# wifi-bt.net
KiCad netlist of a schematic drawn in Altium Designer
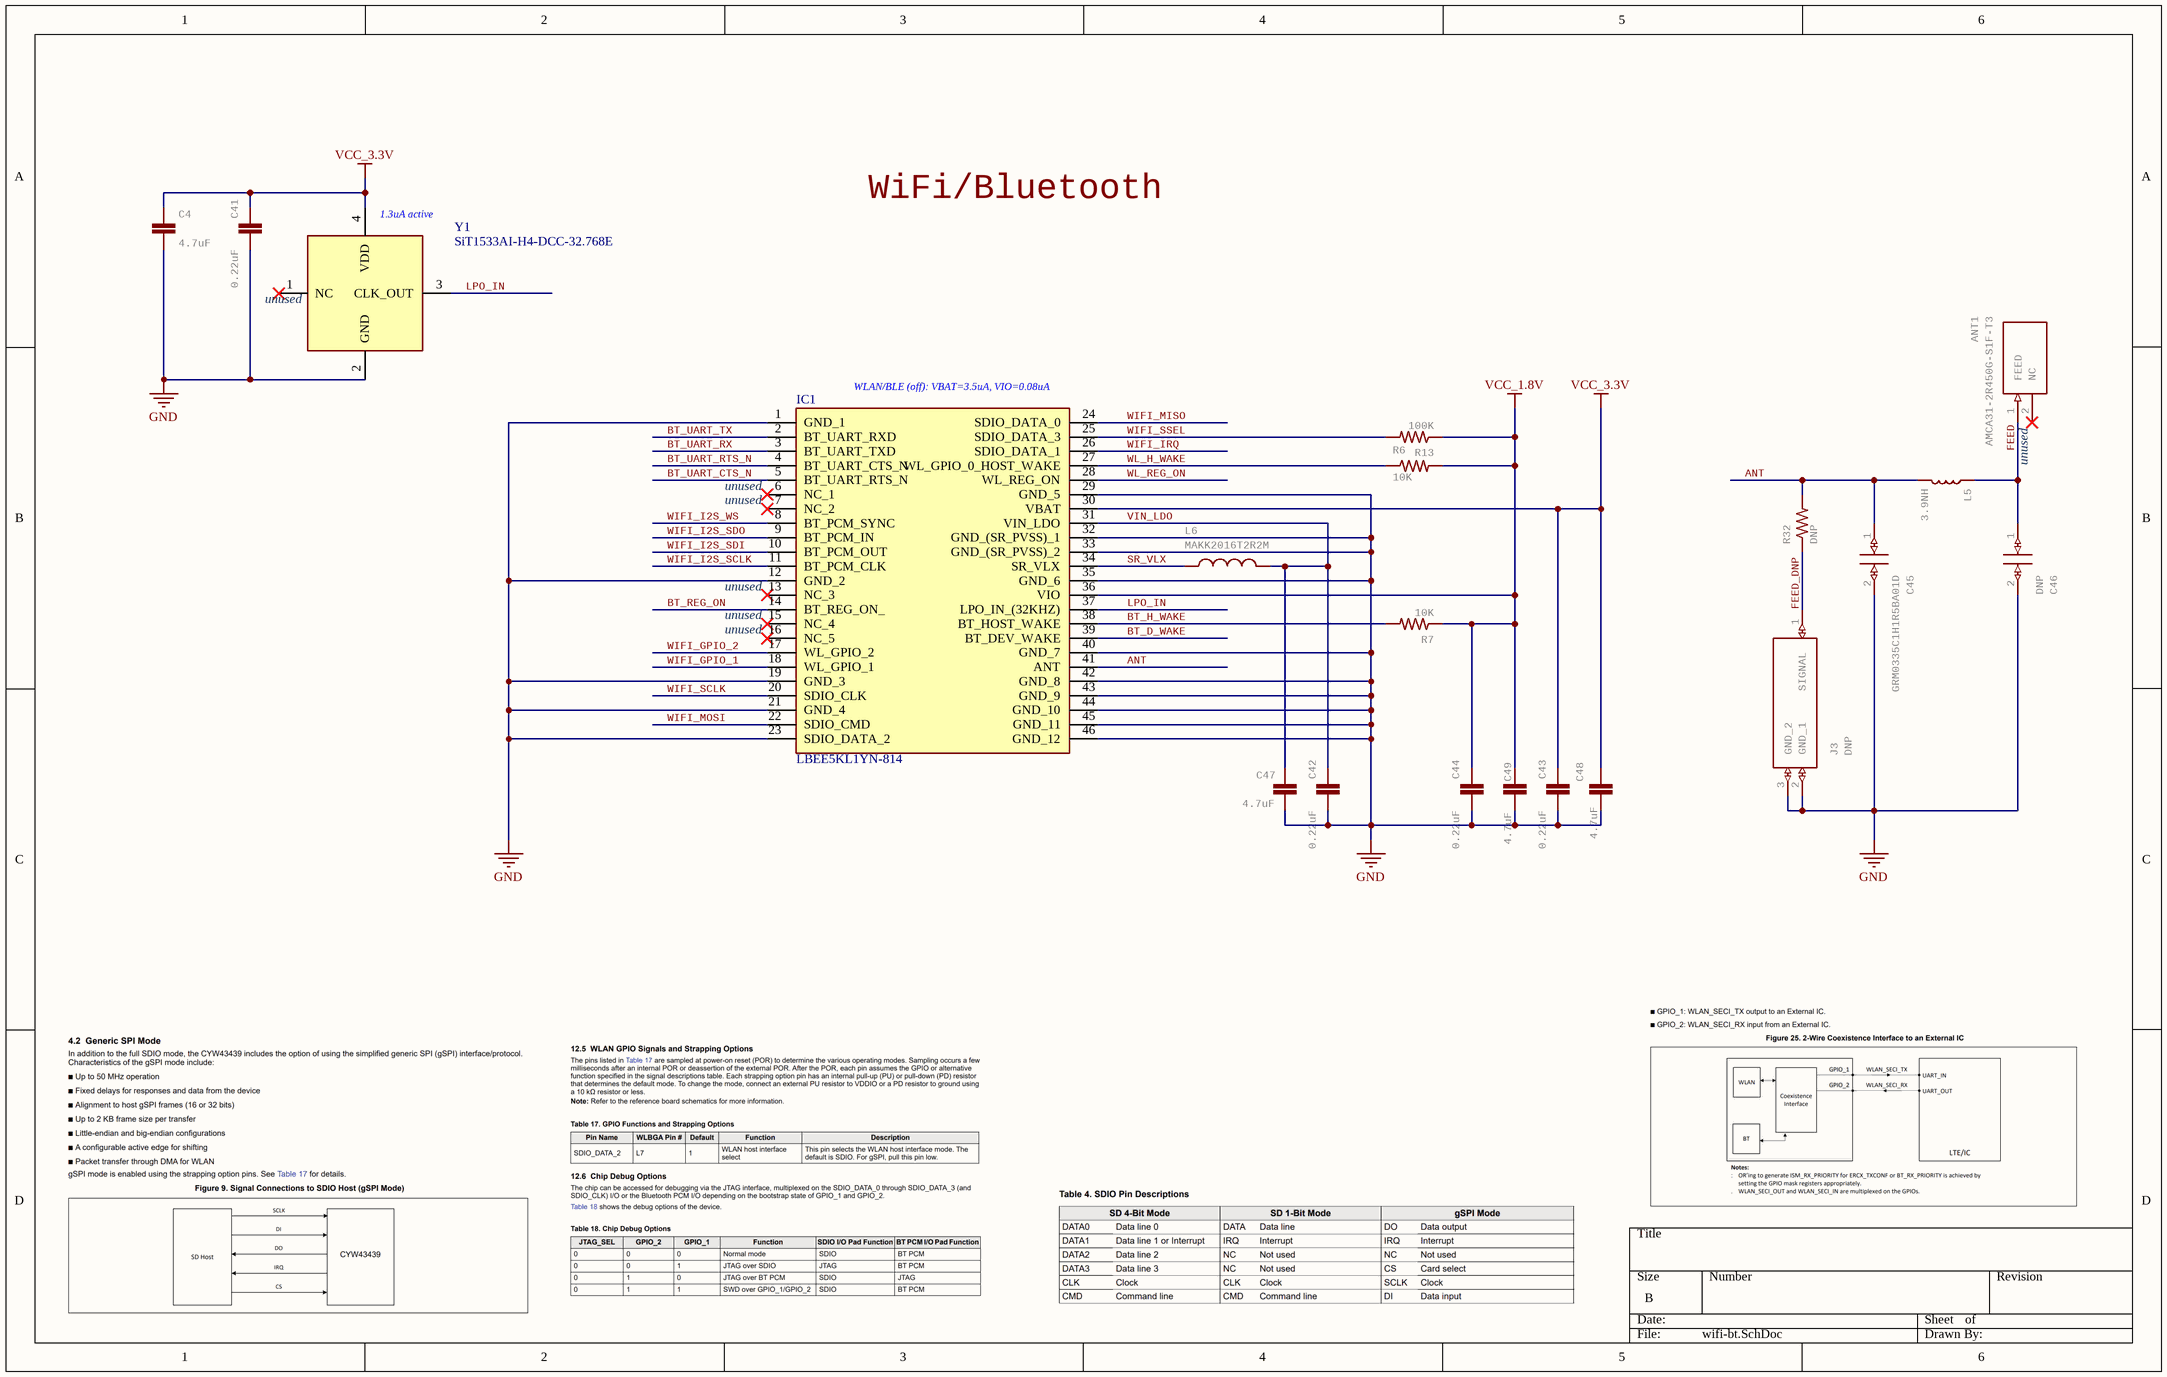
[diagram p0: wifi-bt.SchDoc]

(export (version "E")
  (design (tool "Eeschema 10.0.6"))
  (components
    (comp (ref "ANT1")
      (value "AMCA31-2R450G-S1F-T3")
      (footprint "ANTC3216X140N")
      (description "ABRACON - AMCA31-2R450G-S1F-T3 - ANTENNA, CHIP, 2.45GHZ, 50 OHM, 1206   Source:  Datasheet")
      (fields (field (name "MOUSER_PART_NUMBER") "815-CA312R450GS1FT3"))
      (libsource (lib "openmv-ae3") (part "AMCA31-2R450G-S1F-T3"))
    )
    (comp (ref "C4")
      (value "4.7uF")
      (footprint "0402-CAP")
      (description "CapacitorStandard 0603 ceramic capacitor, and 0.1\" leaded capacitor.")
      (fields (field (name "MPN") "JMK105BBJ475MV-F") (field (name "LIBRARYNAME") "sfe"))
      (libsource (lib "openmv-ae3") (part "CAP0402-CAP"))
    )
    (comp (ref "C41")
      (value "0.22uF")
      (footprint "C0201")
      (description "CAPACITOR, European symbol")
      (fields (field (name "MPN") "GRM033R60J224ME15D"))
      (libsource (lib "openmv-ae3") (part "C-EUC0201"))
    )
    (comp (ref "C42")
      (value "0.22uF")
      (footprint "C0201")
      (description "CAPACITOR, European symbol")
      (fields (field (name "MPN") "GRM033R60J224ME15D"))
      (libsource (lib "openmv-ae3") (part "C-EUC0201"))
    )
    (comp (ref "C43")
      (value "0.22uF")
      (footprint "C0201")
      (description "CAPACITOR, European symbol")
      (fields (field (name "MPN") "GRM033R60J224ME15D"))
      (libsource (lib "openmv-ae3") (part "C-EUC0201"))
    )
    (comp (ref "C44")
      (value "0.22uF")
      (footprint "C0201")
      (description "CAPACITOR, European symbol")
      (fields (field (name "MPN") "GRM033R60J224ME15D"))
      (libsource (lib "openmv-ae3") (part "C-EUC0201"))
    )
    (comp (ref "C45")
      (value "GRM0335C1H1R5BA01D")
      (footprint "CAPC0603X33N")
      (description "Chip Capacitor value 1R5   Source:  Datasheet")
      (fields (field (name "MOUSER_PART_NUMBER") "81-GRM0335C1H1R5BA1D"))
      (libsource (lib "openmv-ae3") (part "GRM0335C1H1R5BA01D"))
    )
    (comp (ref "C46")
      (value "DNP")
      (footprint "C0201-NO-3D")
      (description "Chip Capacitor value 1R5   Source:  Datasheet")
      (fields
        (field (name "MANUFACTURER_PART_NUMBER") "GRM0335C1H1R5BA01D")
        (field (name "MOUSER_PART_NUMBER") "81-GRM0335C1H1R5BA1D")
      )
      (libsource (lib "openmv-ae3") (part "GRM0335C1H1R5BA01D"))
    )
    (comp (ref "C47")
      (value "4.7uF")
      (footprint "0402-CAP")
      (description "CapacitorStandard 0603 ceramic capacitor, and 0.1\" leaded capacitor.")
      (fields (field (name "MPN") "JMK105BBJ475MV-F") (field (name "LIBRARYNAME") "sfe"))
      (libsource (lib "openmv-ae3") (part "CAP0402-CAP"))
    )
    (comp (ref "C48")
      (value "4.7uF")
      (footprint "0402-CAP")
      (description "CapacitorStandard 0603 ceramic capacitor, and 0.1\" leaded capacitor.")
      (fields (field (name "MPN") "JMK105BBJ475MV-F") (field (name "LIBRARYNAME") "sfe"))
      (libsource (lib "openmv-ae3") (part "CAP0402-CAP"))
    )
    (comp (ref "C49")
      (value "4.7uF")
      (footprint "0402-CAP")
      (description "CapacitorStandard 0603 ceramic capacitor, and 0.1\" leaded capacitor.")
      (fields (field (name "MPN") "JMK105BBJ475MV-F") (field (name "LIBRARYNAME") "sfe"))
      (libsource (lib "openmv-ae3") (part "CAP0402-CAP"))
    )
    (comp (ref "IC1")
      (value "LBEE5KL1YN-814")
      (footprint "SamacSys:LBEE5KL1YN814")
      (description "Integrated Circuit")
      (fields (field (name "MOUSER PART NUMBER") "81-LBEE5KL1YN-814"))
      (libsource (lib "openmv-ae3") (part "LBEE5KL1YN-814"))
    )
    (comp (ref "J3")
      (value "DNP")
      (footprint "23370191-NO-3D")
      (description "RF Connectors / Coaxial Connectors MicroCoax receptacle UMCC Gen 1   Source:  Datasheet")
      (fields
        (field (name "MANUFACTURER_PART_NUMBER") "2337019-1")
        (field (name "MOUSER_PART_NUMBER") "571-2337019-1")
      )
      (libsource (lib "openmv-ae3") (part "2337019-1"))
    )
    (comp (ref "L5")
      (value "3.9NH")
      (footprint "0402")
      (fields (field (name "MPN") "L-07C3N9SV6T") (field (name "LIBRARYNAME") "SparkFun-Coils"))
      (libsource (lib "openmv-ae3") (part "INDUCTOR-0402-3.9NH"))
    )
    (comp (ref "L6")
      (value "MAKK2016T2R2M")
      (footprint "INDC2016X100N")
      (description "INDUCTOR, METAL CORE Check availability")
      (fields (field (name "MF") "Taiyo Yuden"))
      (libsource (lib "openmv-ae3") (part "MAKK2016T2R2M"))
    )
    (comp (ref "R6")
      (value "10K")
      (footprint "R0201")
      (fields (field (name "MPN") "RMCF0201FT10K0") (field (name "LIBRARYNAME") "sfe"))
      (libsource (lib "openmv-ae3") (part "RESISTOR0402-RES"))
    )
    (comp (ref "R7")
      (value "10K")
      (footprint "R0201")
      (fields (field (name "MPN") "RMCF0201FT10K0") (field (name "LIBRARYNAME") "sfe"))
      (libsource (lib "openmv-ae3") (part "RESISTOR0402-RES"))
    )
    (comp (ref "R13")
      (value "100K")
      (footprint "R0201")
      (fields (field (name "MPN") "RMCF0201FT100K") (field (name "LIBRARYNAME") "sfe"))
      (libsource (lib "openmv-ae3") (part "RESISTOR0402-RES"))
    )
    (comp (ref "R32")
      (value "DNP")
      (footprint "R0201")
      (fields (field (name "LIBRARYNAME") "sfe"))
      (libsource (lib "openmv-ae3") (part "RESISTOR0402-RES"))
    )
    (comp (ref "Y1")
      (value "SiT1533AI-H4-DCC-32.768E")
      (footprint "SamacSys:SIT1533AIH4AA332768E")
      (description "Crystal or Oscillator")
      (fields (field (name "MOUSER PART NUMBER") "788-1533AIH4DCC32.76"))
      (libsource (lib "openmv-ae3") (part "SIT1533AI-H4-AA3-32.768E"))
    )
  )
  (nets
    (net (code "1") (name "/ANT") (class "Default")
      (node (ref "C45") (pin "1") (pinfunction "1_1") (pintype "bidirectional"))
      (node (ref "IC1") (pin "41") (pinfunction "ANT_41") (pintype "passive"))
      (node (ref "L5") (pin "2") (pinfunction "2_2") (pintype "passive"))
      (node (ref "R32") (pin "2") (pinfunction "2_2") (pintype "passive"))
    )
    (net (code "2") (name "/BT_D_WAKE") (class "Default")
      (node (ref "IC1") (pin "39") (pinfunction "BT_DEV_WAKE_39") (pintype "passive"))
    )
    (net (code "3") (name "/BT_H_WAKE") (class "Default")
      (node (ref "IC1") (pin "38") (pinfunction "BT_HOST_WAKE_38") (pintype "passive"))
      (node (ref "R7") (pin "2") (pinfunction "2_2") (pintype "passive"))
    )
    (net (code "4") (name "/BT_REG_ON") (class "Default")
      (node (ref "IC1") (pin "14") (pinfunction "BT_REG_ON__14") (pintype "passive"))
    )
    (net (code "5") (name "/BT_UART_CTS_N") (class "Default")
      (node (ref "IC1") (pin "5") (pinfunction "BT_UART_RTS_N_5") (pintype "passive"))
    )
    (net (code "6") (name "/BT_UART_RTS_N") (class "Default")
      (node (ref "IC1") (pin "4") (pinfunction "BT_UART_CTS_N_4") (pintype "passive"))
    )
    (net (code "7") (name "/BT_UART_RX") (class "Default")
      (node (ref "IC1") (pin "3") (pinfunction "BT_UART_TXD_3") (pintype "passive"))
    )
    (net (code "8") (name "/BT_UART_TX") (class "Default")
      (node (ref "IC1") (pin "2") (pinfunction "BT_UART_RXD_2") (pintype "passive"))
    )
    (net (code "9") (name "/FEED") (class "Default")
      (node (ref "ANT1") (pin "1") (pinfunction "FEED_1") (pintype "input"))
      (node (ref "C46") (pin "1") (pinfunction "1_1") (pintype "bidirectional"))
      (node (ref "L5") (pin "1") (pinfunction "1_1") (pintype "passive"))
    )
    (net (code "10") (name "/FEED_DNP") (class "Default")
      (node (ref "J3") (pin "1") (pinfunction "SIGNAL_1") (pintype "bidirectional"))
      (node (ref "R32") (pin "1") (pinfunction "1_1") (pintype "passive"))
    )
    (net (code "11") (name "/LPO_IN") (class "Default")
      (node (ref "IC1") (pin "37") (pinfunction "LPO_IN_(32KHZ)_37") (pintype "passive"))
      (node (ref "Y1") (pin "3") (pinfunction "CLK_OUT_3") (pintype "passive"))
    )
    (net (code "12") (name "/SR_VLX") (class "Default")
      (node (ref "IC1") (pin "34") (pinfunction "SR_VLX_34") (pintype "passive"))
      (node (ref "L6") (pin "1") (pinfunction "1_1") (pintype "passive"))
    )
    (net (code "13") (name "/VIN_LDO") (class "Default")
      (node (ref "C42") (pin "1") (pinfunction "1_1") (pintype "passive"))
      (node (ref "C47") (pin "2") (pinfunction "2_2") (pintype "passive"))
      (node (ref "IC1") (pin "31") (pinfunction "VIN_LDO_31") (pintype "passive"))
      (node (ref "L6") (pin "2") (pinfunction "2_2") (pintype "passive"))
    )
    (net (code "14") (name "/WIFI_GPIO_1") (class "Default")
      (node (ref "IC1") (pin "18") (pinfunction "WL_GPIO_1_18") (pintype "passive"))
    )
    (net (code "15") (name "/WIFI_GPIO_2") (class "Default")
      (node (ref "IC1") (pin "17") (pinfunction "WL_GPIO_2_17") (pintype "passive"))
    )
    (net (code "16") (name "/WIFI_I2S_SCLK") (class "Default")
      (node (ref "IC1") (pin "11") (pinfunction "BT_PCM_CLK_11") (pintype "passive"))
    )
    (net (code "17") (name "/WIFI_I2S_SDI") (class "Default")
      (node (ref "IC1") (pin "10") (pinfunction "BT_PCM_OUT_10") (pintype "passive"))
    )
    (net (code "18") (name "/WIFI_I2S_SDO") (class "Default")
      (node (ref "IC1") (pin "9") (pinfunction "BT_PCM_IN_9") (pintype "passive"))
    )
    (net (code "19") (name "/WIFI_I2S_WS") (class "Default")
      (node (ref "IC1") (pin "8") (pinfunction "BT_PCM_SYNC_8") (pintype "passive"))
    )
    (net (code "20") (name "/WIFI_IRQ") (class "Default")
      (node (ref "IC1") (pin "26") (pinfunction "SDIO_DATA_1_26") (pintype "passive"))
    )
    (net (code "21") (name "/WIFI_MISO") (class "Default")
      (node (ref "IC1") (pin "24") (pinfunction "SDIO_DATA_0_24") (pintype "passive"))
    )
    (net (code "22") (name "/WIFI_MOSI") (class "Default")
      (node (ref "IC1") (pin "22") (pinfunction "SDIO_CMD_22") (pintype "passive"))
    )
    (net (code "23") (name "/WIFI_SCLK") (class "Default")
      (node (ref "IC1") (pin "20") (pinfunction "SDIO_CLK_20") (pintype "passive"))
    )
    (net (code "24") (name "/WIFI_SSEL") (class "Default")
      (node (ref "IC1") (pin "25") (pinfunction "SDIO_DATA_3_25") (pintype "passive"))
      (node (ref "R13") (pin "2") (pinfunction "2_2") (pintype "passive"))
    )
    (net (code "25") (name "/WL_H_WAKE") (class "Default")
      (node (ref "IC1") (pin "27") (pinfunction "WL_GPIO_0_HOST_WAKE_27") (pintype "passive"))
      (node (ref "R6") (pin "1") (pinfunction "1_1") (pintype "passive"))
    )
    (net (code "26") (name "/WL_REG_ON") (class "Default")
      (node (ref "IC1") (pin "28") (pinfunction "WL_REG_ON_28") (pintype "passive"))
    )
    (net (code "27") (name "GND") (class "Default")
      (node (ref "C4") (pin "1") (pinfunction "1_1") (pintype "passive"))
      (node (ref "C41") (pin "2") (pinfunction "2_2") (pintype "passive"))
      (node (ref "C42") (pin "2") (pinfunction "2_2") (pintype "passive"))
      (node (ref "C43") (pin "2") (pinfunction "2_2") (pintype "passive"))
      (node (ref "C44") (pin "2") (pinfunction "2_2") (pintype "passive"))
      (node (ref "C45") (pin "2") (pinfunction "2_2") (pintype "bidirectional"))
      (node (ref "C46") (pin "2") (pinfunction "2_2") (pintype "bidirectional"))
      (node (ref "C47") (pin "1") (pinfunction "1_1") (pintype "passive"))
      (node (ref "C48") (pin "1") (pinfunction "1_1") (pintype "passive"))
      (node (ref "C49") (pin "1") (pinfunction "1_1") (pintype "passive"))
      (node (ref "IC1") (pin "1") (pinfunction "GND_1_1") (pintype "passive"))
      (node (ref "IC1") (pin "12") (pinfunction "GND_2_12") (pintype "passive"))
      (node (ref "IC1") (pin "19") (pinfunction "GND_3_19") (pintype "passive"))
      (node (ref "IC1") (pin "21") (pinfunction "GND_4_21") (pintype "passive"))
      (node (ref "IC1") (pin "23") (pinfunction "SDIO_DATA_2_23") (pintype "passive"))
      (node (ref "IC1") (pin "29") (pinfunction "GND_5_29") (pintype "passive"))
      (node (ref "IC1") (pin "32") (pinfunction "GND_(SR_PVSS)_1_32") (pintype "passive"))
      (node (ref "IC1") (pin "33") (pinfunction "GND_(SR_PVSS)_2_33") (pintype "passive"))
      (node (ref "IC1") (pin "35") (pinfunction "GND_6_35") (pintype "passive"))
      (node (ref "IC1") (pin "40") (pinfunction "GND_7_40") (pintype "passive"))
      (node (ref "IC1") (pin "42") (pinfunction "GND_8_42") (pintype "passive"))
      (node (ref "IC1") (pin "43") (pinfunction "GND_9_43") (pintype "passive"))
      (node (ref "IC1") (pin "44") (pinfunction "GND_10_44") (pintype "passive"))
      (node (ref "IC1") (pin "45") (pinfunction "GND_11_45") (pintype "passive"))
      (node (ref "IC1") (pin "46") (pinfunction "GND_12_46") (pintype "passive"))
      (node (ref "J3") (pin "2") (pinfunction "GND_1_2") (pintype "bidirectional"))
      (node (ref "J3") (pin "3") (pinfunction "GND_2_3") (pintype "bidirectional"))
      (node (ref "Y1") (pin "2") (pinfunction "GND_2") (pintype "passive"))
    )
    (net (code "28") (name "VCC_1.8V") (class "Default")
      (node (ref "C44") (pin "1") (pinfunction "1_1") (pintype "passive"))
      (node (ref "C49") (pin "2") (pinfunction "2_2") (pintype "passive"))
      (node (ref "IC1") (pin "36") (pinfunction "VIO_36") (pintype "passive"))
      (node (ref "R13") (pin "1") (pinfunction "1_1") (pintype "passive"))
      (node (ref "R6") (pin "2") (pinfunction "2_2") (pintype "passive"))
      (node (ref "R7") (pin "1") (pinfunction "1_1") (pintype "passive"))
    )
    (net (code "29") (name "VCC_3.3V") (class "Default")
      (node (ref "C4") (pin "2") (pinfunction "2_2") (pintype "passive"))
      (node (ref "C41") (pin "1") (pinfunction "1_1") (pintype "passive"))
      (node (ref "C43") (pin "1") (pinfunction "1_1") (pintype "passive"))
      (node (ref "C48") (pin "2") (pinfunction "2_2") (pintype "passive"))
      (node (ref "IC1") (pin "30") (pinfunction "VBAT_30") (pintype "passive"))
      (node (ref "Y1") (pin "4") (pinfunction "VDD_4") (pintype "passive"))
    )
    (net (code "30") (name "unconnected-(ANT1-NC-Pad2)") (class "Default")
      (node (ref "ANT1") (pin "2") (pinfunction "NC_2") (pintype "passive+no_connect"))
    )
    (net (code "31") (name "unconnected-(IC1-NC_1-Pad6)") (class "Default")
      (node (ref "IC1") (pin "6") (pinfunction "NC_1_6") (pintype "passive+no_connect"))
    )
    (net (code "32") (name "unconnected-(IC1-NC_2-Pad7)") (class "Default")
      (node (ref "IC1") (pin "7") (pinfunction "NC_2_7") (pintype "passive+no_connect"))
    )
    (net (code "33") (name "unconnected-(IC1-NC_3-Pad13)") (class "Default")
      (node (ref "IC1") (pin "13") (pinfunction "NC_3_13") (pintype "passive+no_connect"))
    )
    (net (code "34") (name "unconnected-(IC1-NC_4-Pad15)") (class "Default")
      (node (ref "IC1") (pin "15") (pinfunction "NC_4_15") (pintype "passive+no_connect"))
    )
    (net (code "35") (name "unconnected-(IC1-NC_5-Pad16)") (class "Default")
      (node (ref "IC1") (pin "16") (pinfunction "NC_5_16") (pintype "passive+no_connect"))
    )
    (net (code "36") (name "unconnected-(Y1-NC-Pad1)") (class "Default")
      (node (ref "Y1") (pin "1") (pinfunction "NC_1") (pintype "passive+no_connect"))
    )
  )
)
